# design.net
KiCad netlist of a schematic drawn in Altium Designer
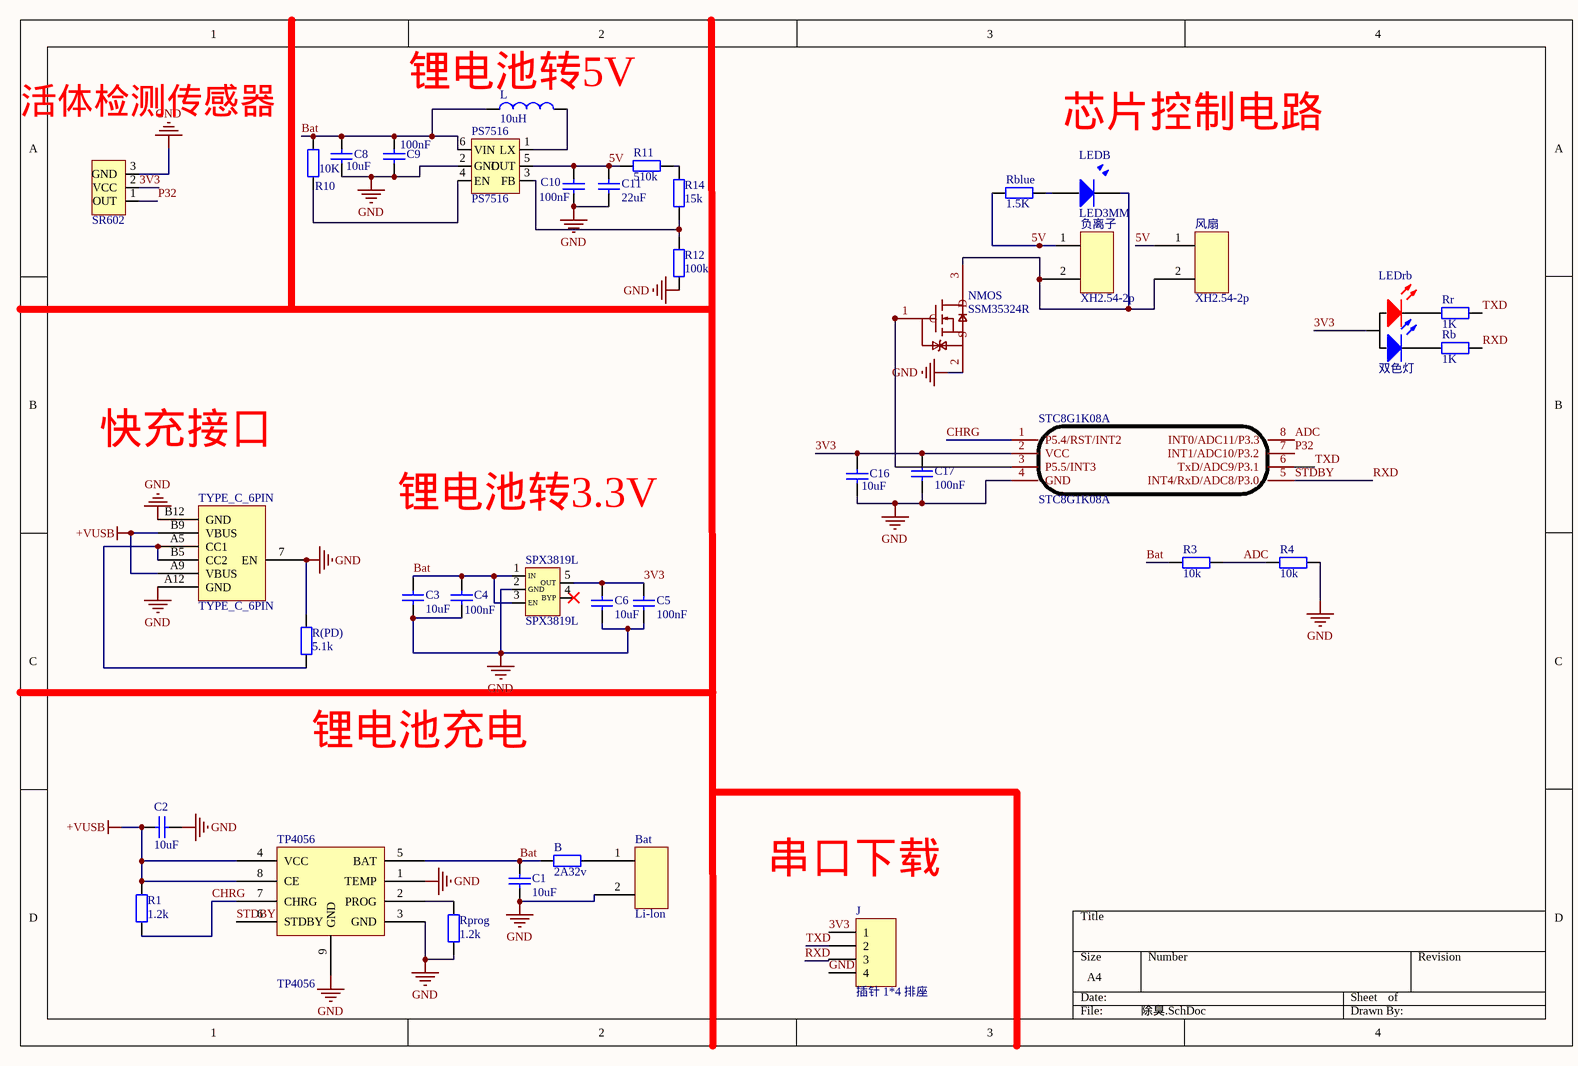
[diagram p0: 除臭.SchDoc]

(export (version "E")
  (design (tool "Eeschema 10.0.6"))
  (components
    (comp (ref "B") (value "2A32v") (footprint "0603 电阻") (libsource (lib "") (part "电阻_2")))
    (comp (ref "Bat")
      (value "Li-lon")
      (footprint "XH-2.54-2p")
      (libsource (lib "原理图库_张赛豪") (part "XH2.54-2p"))
    )
    (comp (ref "C1") (value "10uF") (footprint "0603 电容") (libsource (lib "原理图库--郭庆鹏") (part "电容 无极")))
    (comp (ref "C2") (value "10uF") (footprint "0603 电容") (libsource (lib "原理图库--郭庆鹏") (part "电容 无极")))
    (comp (ref "C3") (value "10uF") (footprint "0603 电容") (libsource (lib "原理图库--郭庆鹏") (part "电容 无极")))
    (comp (ref "C4") (value "100nF") (footprint "0603 电容") (libsource (lib "原理图库--郭庆鹏") (part "电容 无极")))
    (comp (ref "C5") (value "100nF") (footprint "0603 电容") (libsource (lib "原理图库--郭庆鹏") (part "电容 无极")))
    (comp (ref "C6") (value "10uF") (footprint "0603 电容") (libsource (lib "原理图库--郭庆鹏") (part "电容 无极")))
    (comp (ref "C8") (value "10uF") (footprint "0603 电容") (libsource (lib "原理图库--郭庆鹏") (part "电容 无极")))
    (comp (ref "C9") (value "100nF") (footprint "0603 电容") (libsource (lib "原理图库--郭庆鹏") (part "电容 无极")))
    (comp (ref "C10") (value "100nF") (footprint "0603 电容") (libsource (lib "原理图库--郭庆鹏") (part "电容 无极")))
    (comp (ref "C11") (value "22uF") (footprint "0603 电容") (libsource (lib "原理图库--郭庆鹏") (part "电容 无极")))
    (comp (ref "C16") (value "10uF") (footprint "0603 电容") (libsource (lib "原理图库--郭庆鹏") (part "电容 无极")))
    (comp (ref "C17") (value "100nF") (footprint "0603 电容") (libsource (lib "原理图库--郭庆鹏") (part "电容 无极")))
    (comp (ref "J") (value "插针 1*4 排座") (footprint "插针1*4") (libsource (lib "5") (part "插针 1*4 排座")))
    (comp (ref "L") (value "10uH") (footprint "电感 贴片 6*6") (libsource (lib "原理图库--郭庆鹏") (part "电感")))
    (comp (ref "LEDB") (value "LED3MM") (footprint "LED3MM") (libsource (lib "原理图库_张赛豪") (part "LED3MM")))
    (comp (ref "LEDrb") (value "双色灯") (footprint "双色LED_F3") (libsource (lib "原理图库_张赛豪") (part "双色灯")))
    (comp (ref "NMOS") (value "SSM35324R") (footprint "NOMOS") (libsource (lib "原理图库_张赛豪") (part "NMOS")))
    (comp (ref "PS7516") (value "PS7516") (footprint "PS7516") (libsource (lib "原理图库_张赛豪") (part "PS7516")))
    (comp (ref "R(PD)") (value "5.1k") (footprint "0603 电阻") (libsource (lib "原理图库--郭庆鹏") (part "电阻")))
    (comp (ref "R1") (value "1.2k") (footprint "0603 电阻") (libsource (lib "原理图库--郭庆鹏") (part "电阻")))
    (comp (ref "R3") (value "10k") (footprint "0603 电阻") (libsource (lib "") (part "电阻_1")))
    (comp (ref "R4") (value "10k") (footprint "0603 电阻") (libsource (lib "") (part "电阻_1")))
    (comp (ref "R10") (value "10K") (footprint "0603 电阻") (libsource (lib "原理图库--郭庆鹏") (part "电阻")))
    (comp (ref "R11") (value "510k") (footprint "0603 电阻") (libsource (lib "") (part "电阻_1")))
    (comp (ref "R12") (value "100k") (footprint "0603 电阻") (libsource (lib "原理图库--郭庆鹏") (part "电阻")))
    (comp (ref "R14") (value "15k") (footprint "0603 电阻") (libsource (lib "") (part "电阻_3")))
    (comp (ref "Rb") (value "1K") (footprint "0603 电阻") (libsource (lib "") (part "电阻_1")))
    (comp (ref "Rblue") (value "1.5K") (footprint "0603 电阻") (libsource (lib "") (part "电阻_1")))
    (comp (ref "Rprog") (value "1.2k") (footprint "0603 电阻") (libsource (lib "原理图库--郭庆鹏") (part "电阻")))
    (comp (ref "Rr") (value "1K") (footprint "0603 电阻") (libsource (lib "") (part "电阻_1")))
    (comp (ref "SPX3819L")
      (value "SPX3819L")
      (footprint "SPX3819")
      (libsource (lib "原理图库_张赛豪") (part "SPX3819LM"))
    )
    (comp (ref "SR602") (value "SR602") (footprint "SR602") (libsource (lib "原理图库_张赛豪") (part "SR602")))
    (comp (ref "STC8G1K08A")
      (value "STC8G1K08A")
      (footprint "STC8G1K08A")
      (libsource (lib "原理图库_张赛豪") (part "STC8G1K08A"))
    )
    (comp (ref "TP4056") (value "TP4056") (footprint "TP4056") (libsource (lib "原理图库_张赛豪") (part "TP4056")))
    (comp (ref "TYPE_C_6PIN")
      (value "TYPE_C_6PIN")
      (footprint "TYPE_C_PIN")
      (libsource (lib "原理图库_张赛豪") (part "TYPE_C_6PIN"))
    )
    (comp (ref "负离子")
      (value "XH2.54-2p")
      (footprint "XH-2.54-2p")
      (libsource (lib "原理图库_张赛豪") (part "XH2.54-2p"))
    )
    (comp (ref "风扇")
      (value "XH2.54-2p")
      (footprint "XH-2.54-2p")
      (libsource (lib "原理图库_张赛豪") (part "XH2.54-2p"))
    )
  )
  (nets
    (net (code "1") (name "+VUSB") (class "Default")
      (node (ref "C2") (pin "2") (pinfunction "2_2") (pintype "passive"))
      (node (ref "R1") (pin "2") (pinfunction "2_2") (pintype "passive"))
      (node (ref "TP4056") (pin "4") (pinfunction "VCC_4") (pintype "passive"))
      (node (ref "TP4056") (pin "8") (pinfunction "CE_8") (pintype "passive"))
      (node (ref "TYPE_C_6PIN") (pin "A9") (pinfunction "VBUS_A9") (pintype "passive"))
      (node (ref "TYPE_C_6PIN") (pin "B9") (pinfunction "VBUS_B9") (pintype "passive"))
    )
    (net (code "2") (name "/3V3") (class "Default")
      (node (ref "C16") (pin "2") (pinfunction "2_2") (pintype "passive"))
      (node (ref "C17") (pin "2") (pinfunction "2_2") (pintype "passive"))
      (node (ref "C5") (pin "2") (pinfunction "2_2") (pintype "passive"))
      (node (ref "C6") (pin "2") (pinfunction "2_2") (pintype "passive"))
      (node (ref "J") (pin "1") (pinfunction "1_1") (pintype "passive"))
      (node (ref "LEDrb") (pin "3") (pinfunction "VCC_3") (pintype "passive"))
      (node (ref "SPX3819L") (pin "5") (pinfunction "OUT_5") (pintype "passive"))
      (node (ref "SR602") (pin "2") (pinfunction "VCC_2") (pintype "passive"))
      (node (ref "STC8G1K08A") (pin "2") (pinfunction "VCC_2") (pintype "passive"))
    )
    (net (code "3") (name "/5V") (class "Default")
      (node (ref "C10") (pin "2") (pinfunction "2_2") (pintype "passive"))
      (node (ref "C11") (pin "2") (pinfunction "2_2") (pintype "passive"))
      (node (ref "PS7516") (pin "5") (pinfunction "OUT_5") (pintype "passive"))
      (node (ref "R11") (pin "2") (pinfunction "2_2") (pintype "passive"))
      (node (ref "Rblue") (pin "2") (pinfunction "2_2") (pintype "passive"))
      (node (ref "负离子") (pin "1") (pinfunction "1_1") (pintype "passive"))
      (node (ref "风扇") (pin "1") (pinfunction "1_1") (pintype "passive"))
    )
    (net (code "4") (name "/ADC") (class "Default")
      (node (ref "R3") (pin "1") (pinfunction "1_1") (pintype "passive"))
      (node (ref "R4") (pin "2") (pinfunction "2_2") (pintype "passive"))
      (node (ref "STC8G1K08A") (pin "8") (pinfunction "INT0/ADC11/P3.3_8") (pintype "passive"))
    )
    (net (code "5") (name "/Bat") (class "Default")
      (node (ref "B") (pin "1") (pinfunction "1_1") (pintype "passive"))
      (node (ref "C1") (pin "2") (pinfunction "2_2") (pintype "passive"))
      (node (ref "C3") (pin "2") (pinfunction "2_2") (pintype "passive"))
      (node (ref "C4") (pin "2") (pinfunction "2_2") (pintype "passive"))
      (node (ref "C8") (pin "2") (pinfunction "2_2") (pintype "passive"))
      (node (ref "C9") (pin "2") (pinfunction "2_2") (pintype "passive"))
      (node (ref "L") (pin "1") (pinfunction "1_1") (pintype "passive"))
      (node (ref "PS7516") (pin "6") (pinfunction "VIN_6") (pintype "passive"))
      (node (ref "R10") (pin "2") (pinfunction "2_2") (pintype "passive"))
      (node (ref "R3") (pin "2") (pinfunction "2_2") (pintype "passive"))
      (node (ref "SPX3819L") (pin "1") (pinfunction "IN_1") (pintype "passive"))
      (node (ref "SPX3819L") (pin "3") (pinfunction "EN_3") (pintype "passive"))
      (node (ref "TP4056") (pin "5") (pinfunction "BAT_5") (pintype "passive"))
    )
    (net (code "6") (name "/CHRG") (class "Default")
      (node (ref "R1") (pin "1") (pinfunction "1_1") (pintype "passive"))
      (node (ref "STC8G1K08A") (pin "1") (pinfunction "P5.4/RST/INT2_1") (pintype "passive"))
      (node (ref "TP4056") (pin "7") (pinfunction "CHRG_7") (pintype "passive"))
    )
    (net (code "7") (name "/P32") (class "Default")
      (node (ref "SR602") (pin "1") (pinfunction "OUT_1") (pintype "passive"))
      (node (ref "STC8G1K08A") (pin "7") (pinfunction "INT1/ADC10/P3.2_7") (pintype "passive"))
    )
    (net (code "8") (name "/RXD") (class "Default")
      (node (ref "J") (pin "3") (pinfunction "3_3") (pintype "passive"))
      (node (ref "Rb") (pin "1") (pinfunction "1_1") (pintype "passive"))
      (node (ref "STC8G1K08A") (pin "5") (pinfunction "INT4/RxD/ADC8/P3.0_5") (pintype "passive"))
      (node (ref "TP4056") (pin "6") (pinfunction "STDBY_6") (pintype "passive"))
    )
    (net (code "9") (name "/TXD") (class "Default")
      (node (ref "J") (pin "2") (pinfunction "2_2") (pintype "passive"))
      (node (ref "Rr") (pin "1") (pinfunction "1_1") (pintype "passive"))
      (node (ref "STC8G1K08A") (pin "6") (pinfunction "TxD/ADC9/P3.1_6") (pintype "passive"))
    )
    (net (code "10") (name "GND") (class "Default")
      (node (ref "Bat") (pin "2") (pinfunction "2_2") (pintype "passive"))
      (node (ref "C1") (pin "1") (pinfunction "1_1") (pintype "passive"))
      (node (ref "C10") (pin "1") (pinfunction "1_1") (pintype "passive"))
      (node (ref "C11") (pin "1") (pinfunction "1_1") (pintype "passive"))
      (node (ref "C16") (pin "1") (pinfunction "1_1") (pintype "passive"))
      (node (ref "C17") (pin "1") (pinfunction "1_1") (pintype "passive"))
      (node (ref "C2") (pin "1") (pinfunction "1_1") (pintype "passive"))
      (node (ref "C3") (pin "1") (pinfunction "1_1") (pintype "passive"))
      (node (ref "C4") (pin "1") (pinfunction "1_1") (pintype "passive"))
      (node (ref "C5") (pin "1") (pinfunction "1_1") (pintype "passive"))
      (node (ref "C6") (pin "1") (pinfunction "1_1") (pintype "passive"))
      (node (ref "C8") (pin "1") (pinfunction "1_1") (pintype "passive"))
      (node (ref "C9") (pin "1") (pinfunction "1_1") (pintype "passive"))
      (node (ref "J") (pin "4") (pinfunction "4_4") (pintype "passive"))
      (node (ref "NMOS") (pin "2") (pinfunction "S_2") (pintype "passive"))
      (node (ref "PS7516") (pin "2") (pinfunction "GND_2") (pintype "passive"))
      (node (ref "R(PD)") (pin "2") (pinfunction "2_2") (pintype "passive"))
      (node (ref "R12") (pin "1") (pinfunction "1_1") (pintype "passive"))
      (node (ref "R4") (pin "1") (pinfunction "1_1") (pintype "passive"))
      (node (ref "Rprog") (pin "1") (pinfunction "1_1") (pintype "passive"))
      (node (ref "SPX3819L") (pin "2") (pinfunction "GND_2") (pintype "passive"))
      (node (ref "SR602") (pin "3") (pinfunction "GND_3") (pintype "passive"))
      (node (ref "STC8G1K08A") (pin "4") (pinfunction "GND_4") (pintype "passive"))
      (node (ref "TP4056") (pin "1") (pinfunction "TEMP_1") (pintype "passive"))
      (node (ref "TP4056") (pin "3") (pinfunction "GND_3") (pintype "passive"))
      (node (ref "TP4056") (pin "9") (pinfunction "GND_9") (pintype "passive"))
      (node (ref "TYPE_C_6PIN") (pin "7") (pinfunction "EN_7") (pintype "passive"))
      (node (ref "TYPE_C_6PIN") (pin "A12") (pinfunction "GND_A12") (pintype "passive"))
      (node (ref "TYPE_C_6PIN") (pin "B12") (pinfunction "GND_B12") (pintype "passive"))
    )
    (net (code "11") (name "Net-(B-Pad2)") (class "Default")
      (node (ref "B") (pin "2") (pinfunction "2_2") (pintype "passive"))
      (node (ref "Bat") (pin "1") (pinfunction "1_1") (pintype "passive"))
    )
    (net (code "12") (name "Net-(LEDB-Pad1)") (class "Default")
      (node (ref "LEDB") (pin "1") (pinfunction "1_1") (pintype "passive"))
      (node (ref "Rblue") (pin "1") (pinfunction "1_1") (pintype "passive"))
    )
    (net (code "13") (name "Net-(LEDrb-B)") (class "Default")
      (node (ref "LEDrb") (pin "2") (pinfunction "B_2") (pintype "passive"))
      (node (ref "Rb") (pin "2") (pinfunction "2_2") (pintype "passive"))
    )
    (net (code "14") (name "Net-(LEDrb-R)") (class "Default")
      (node (ref "LEDrb") (pin "1") (pinfunction "R_1") (pintype "passive"))
      (node (ref "Rr") (pin "2") (pinfunction "2_2") (pintype "passive"))
    )
    (net (code "15") (name "Net-(NMOS-D)") (class "Default")
      (node (ref "LEDB") (pin "2") (pinfunction "2_2") (pintype "passive"))
      (node (ref "NMOS") (pin "3") (pinfunction "D_3") (pintype "passive"))
      (node (ref "负离子") (pin "2") (pinfunction "2_2") (pintype "passive"))
      (node (ref "风扇") (pin "2") (pinfunction "2_2") (pintype "passive"))
    )
    (net (code "16") (name "Net-(NMOS-G)") (class "Default")
      (node (ref "NMOS") (pin "1") (pinfunction "G_1") (pintype "passive"))
      (node (ref "STC8G1K08A") (pin "3") (pinfunction "P5.5/INT3_3") (pintype "passive"))
    )
    (net (code "17") (name "Net-(PS7516-EN)") (class "Default")
      (node (ref "PS7516") (pin "4") (pinfunction "EN_4") (pintype "passive"))
      (node (ref "R10") (pin "1") (pinfunction "1_1") (pintype "passive"))
    )
    (net (code "18") (name "Net-(PS7516-FB)") (class "Default")
      (node (ref "PS7516") (pin "3") (pinfunction "FB_3") (pintype "passive"))
      (node (ref "R12") (pin "2") (pinfunction "2_2") (pintype "passive"))
      (node (ref "R14") (pin "2") (pinfunction "2_2") (pintype "passive"))
    )
    (net (code "19") (name "Net-(PS7516-LX)") (class "Default")
      (node (ref "L") (pin "2") (pinfunction "2_2") (pintype "passive"))
      (node (ref "PS7516") (pin "1") (pinfunction "LX_1") (pintype "passive"))
    )
    (net (code "20") (name "Net-(R11-Pad1)") (class "Default")
      (node (ref "R11") (pin "1") (pinfunction "1_1") (pintype "passive"))
      (node (ref "R14") (pin "1") (pinfunction "1_1") (pintype "passive"))
    )
    (net (code "21") (name "Net-(TP4056-PROG)") (class "Default")
      (node (ref "Rprog") (pin "2") (pinfunction "2_2") (pintype "passive"))
      (node (ref "TP4056") (pin "2") (pinfunction "PROG_2") (pintype "passive"))
    )
    (net (code "22") (name "Net-(TYPE_C_6PIN-CC1)") (class "Default")
      (node (ref "R(PD)") (pin "1") (pinfunction "1_1") (pintype "passive"))
      (node (ref "TYPE_C_6PIN") (pin "A5") (pinfunction "CC1_A5") (pintype "passive"))
      (node (ref "TYPE_C_6PIN") (pin "B5") (pinfunction "CC2_B5") (pintype "passive"))
    )
    (net (code "23") (name "unconnected-(SPX3819L-BYP-Pad4)") (class "Default")
      (node (ref "SPX3819L") (pin "4") (pinfunction "BYP_4") (pintype "passive+no_connect"))
    )
  )
)
